# MCU.net
KiCad netlist of a schematic drawn in Altium Designer
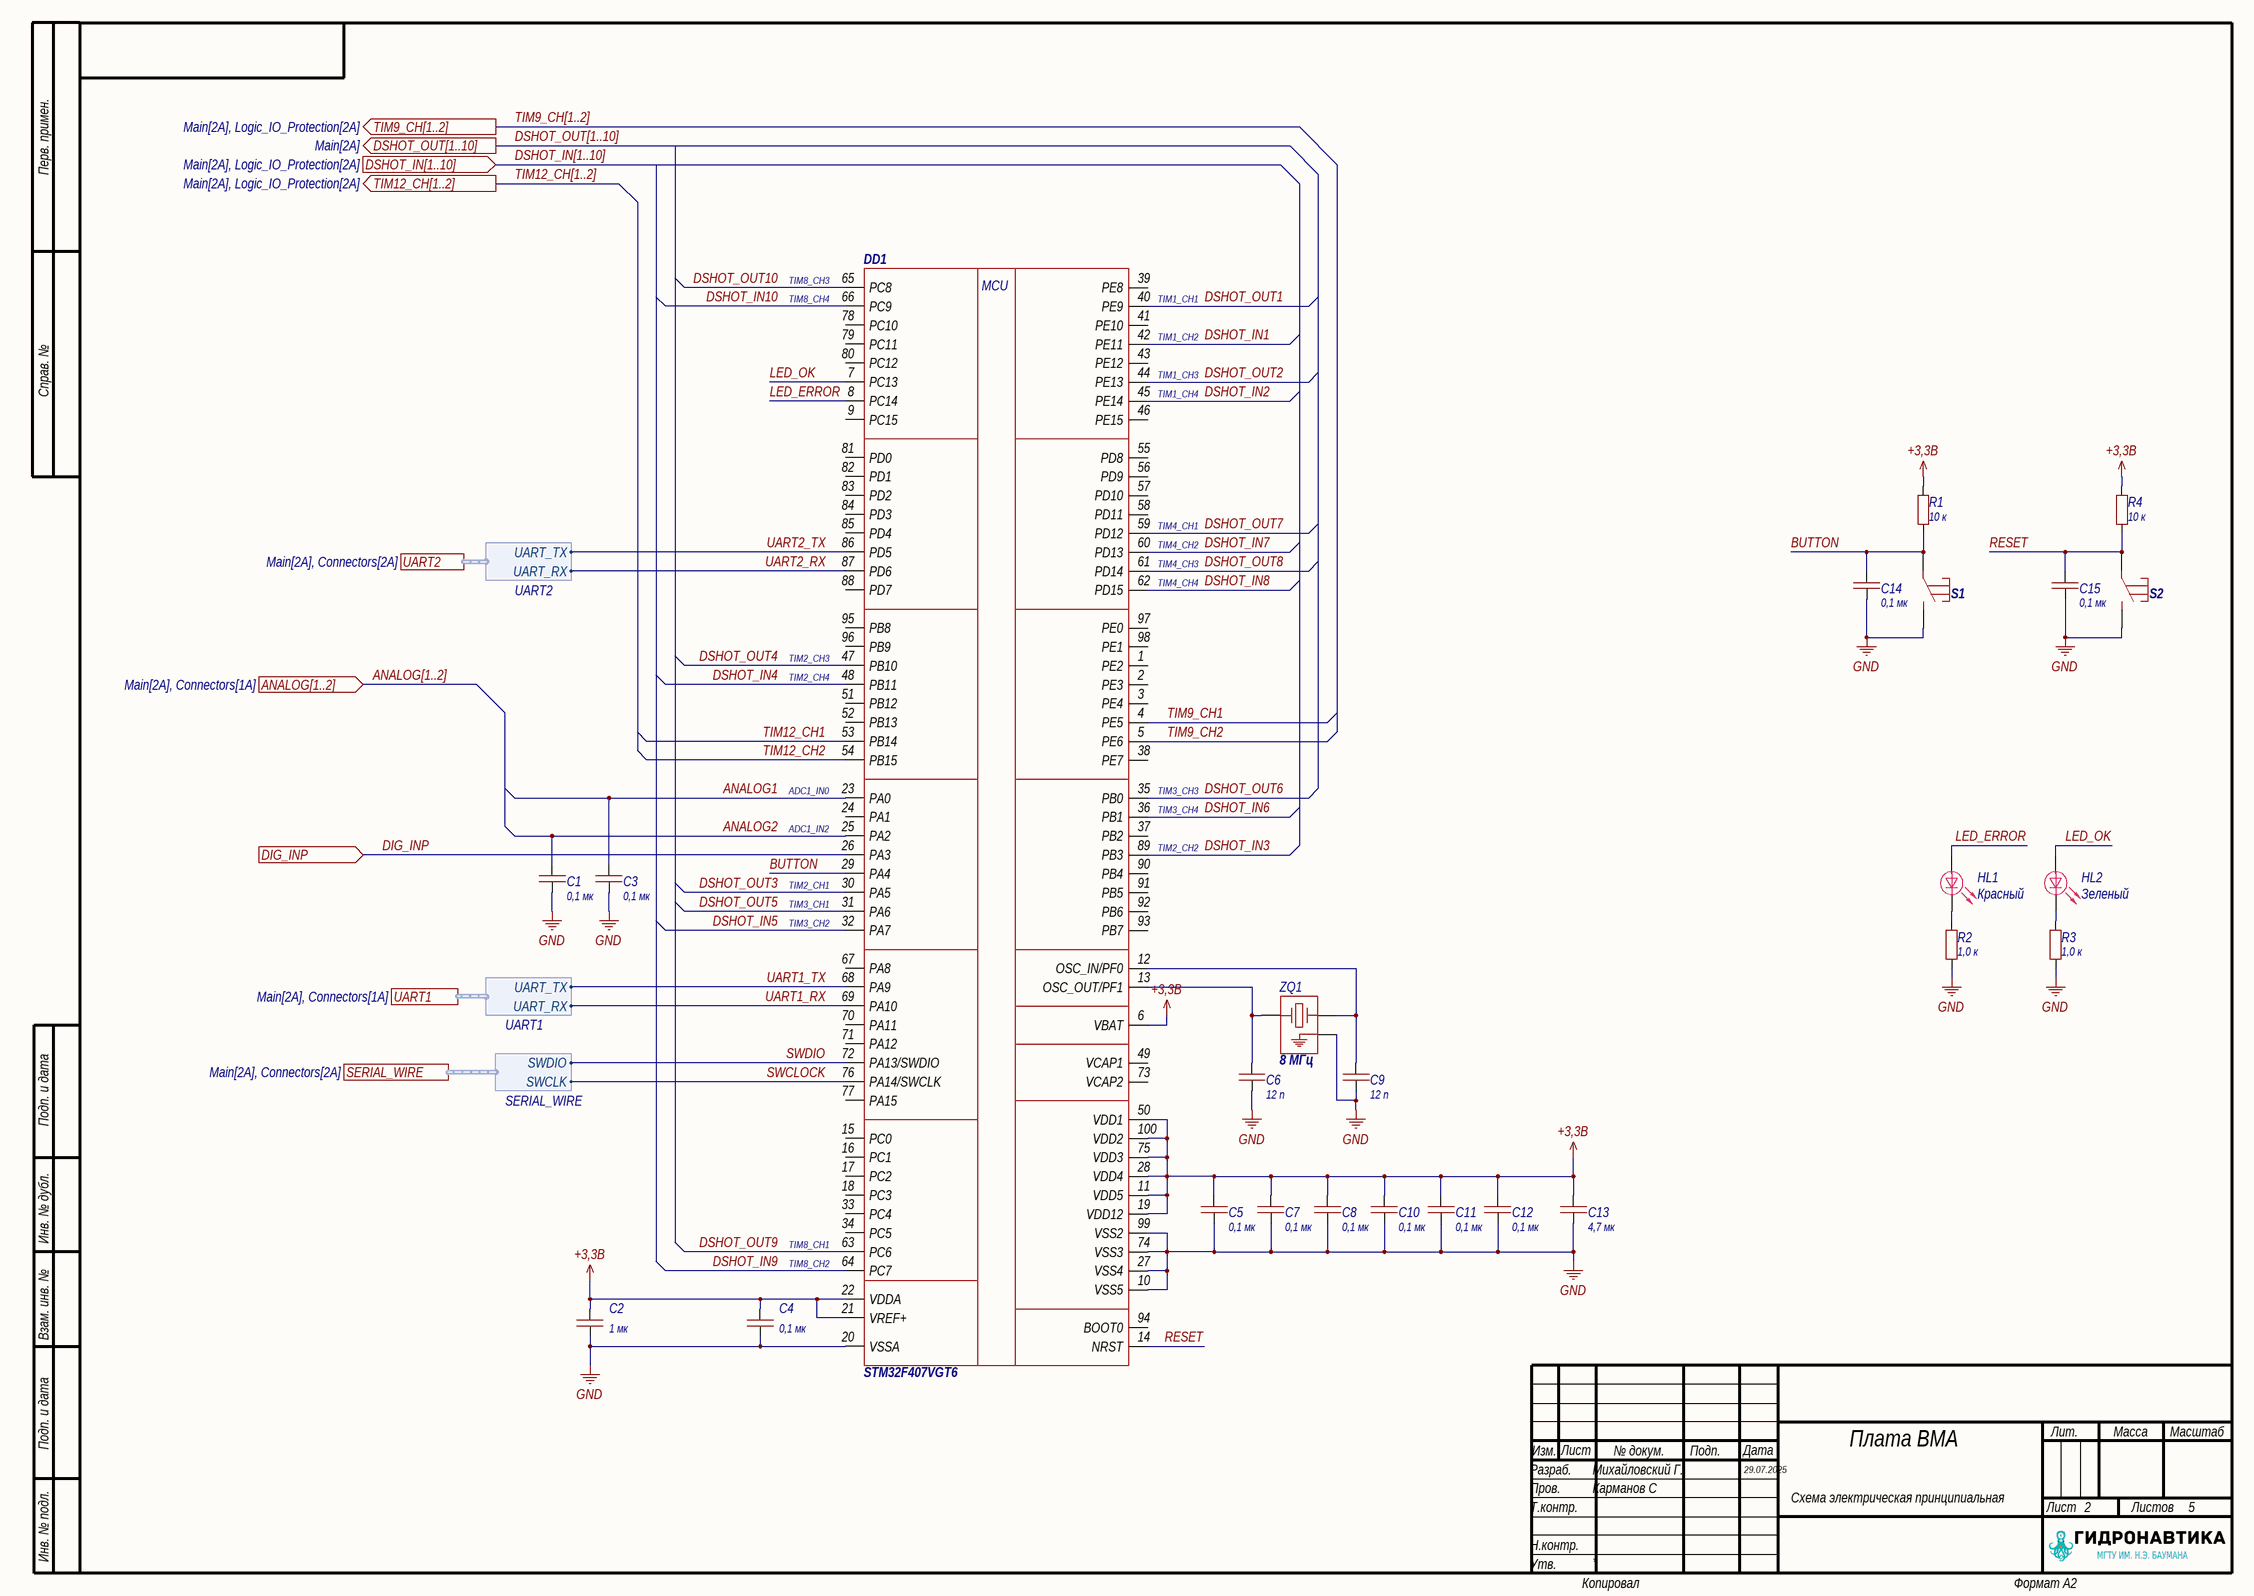
[diagram p0: MCU.SchDoc]

(export (version "E")
  (design (tool "Eeschema 10.0.6"))
  (components
    (comp (ref "C1")
      (value "0,1 мк")
      (footprint "0603C")
      (description "Конденсатор")
      (fields (field (name "PART NUMBER") "Capacitor_0,1u_10_50V_X7R_0603C") (field (name "TOLERANCE") "0,1"))
      (libsource (lib "Hydrolib") (part "Capacitor"))
    )
    (comp (ref "C2")
      (value "1 мк")
      (footprint "0603C")
      (description "Конденсатор")
      (fields (field (name "PART NUMBER") "Capacitor_1u_10_50V_X7R_0603C") (field (name "TOLERANCE") "0,1"))
      (libsource (lib "Hydrolib") (part "Capacitor"))
    )
    (comp (ref "C3")
      (value "0,1 мк")
      (footprint "0603C")
      (description "Конденсатор")
      (fields (field (name "PART NUMBER") "Capacitor_0,1u_10_50V_X7R_0603C") (field (name "TOLERANCE") "0,1"))
      (libsource (lib "Hydrolib") (part "Capacitor"))
    )
    (comp (ref "C4")
      (value "0,1 мк")
      (footprint "0603C")
      (description "Конденсатор")
      (fields (field (name "PART NUMBER") "Capacitor_0,1u_10_50V_X7R_0603C") (field (name "TOLERANCE") "0,1"))
      (libsource (lib "Hydrolib") (part "Capacitor"))
    )
    (comp (ref "C5")
      (value "0,1 мк")
      (footprint "0603C")
      (description "Конденсатор")
      (fields (field (name "PART NUMBER") "Capacitor_0,1u_10_50V_X7R_0603C") (field (name "TOLERANCE") "0,1"))
      (libsource (lib "Hydrolib") (part "Capacitor"))
    )
    (comp (ref "C6")
      (value "12 п")
      (footprint "0603C")
      (description "Конденсатор 12п")
      (fields (field (name "PART NUMBER") "Capacitor"))
      (libsource (lib "Hydrolib") (part "Capacitor"))
    )
    (comp (ref "C7")
      (value "0,1 мк")
      (footprint "0603C")
      (description "Конденсатор")
      (fields (field (name "PART NUMBER") "Capacitor_0,1u_10_50V_X7R_0603C") (field (name "TOLERANCE") "0,1"))
      (libsource (lib "Hydrolib") (part "Capacitor"))
    )
    (comp (ref "C8")
      (value "0,1 мк")
      (footprint "0603C")
      (description "Конденсатор")
      (fields (field (name "PART NUMBER") "Capacitor_0,1u_10_50V_X7R_0603C") (field (name "TOLERANCE") "0,1"))
      (libsource (lib "Hydrolib") (part "Capacitor"))
    )
    (comp (ref "C9")
      (value "12 п")
      (footprint "0603C")
      (description "Конденсатор 12п")
      (fields (field (name "PART NUMBER") "Capacitor"))
      (libsource (lib "Hydrolib") (part "Capacitor"))
    )
    (comp (ref "C10")
      (value "0,1 мк")
      (footprint "0603C")
      (description "Конденсатор")
      (fields (field (name "PART NUMBER") "Capacitor_0,1u_10_50V_X7R_0603C") (field (name "TOLERANCE") "0,1"))
      (libsource (lib "Hydrolib") (part "Capacitor"))
    )
    (comp (ref "C11")
      (value "0,1 мк")
      (footprint "0603C")
      (description "Конденсатор")
      (fields (field (name "PART NUMBER") "Capacitor_0,1u_10_50V_X7R_0603C") (field (name "TOLERANCE") "0,1"))
      (libsource (lib "Hydrolib") (part "Capacitor"))
    )
    (comp (ref "C12")
      (value "0,1 мк")
      (footprint "0603C")
      (description "Конденсатор")
      (fields (field (name "PART NUMBER") "Capacitor_0,1u_10_50V_X7R_0603C") (field (name "TOLERANCE") "0,1"))
      (libsource (lib "Hydrolib") (part "Capacitor"))
    )
    (comp (ref "C13")
      (value "4,7 мк")
      (footprint "1206C")
      (description "Конденсатор")
      (fields (field (name "PART NUMBER") "Capacitor_4,7u_10_50V_X7R_1206C") (field (name "TOLERANCE") "0,1"))
      (libsource (lib "Hydrolib") (part "Capacitor"))
    )
    (comp (ref "C14")
      (value "0,1 мк")
      (footprint "0603C")
      (description "Конденсатор")
      (fields (field (name "PART NUMBER") "Capacitor_0,1u_10_50V_X7R_0603C") (field (name "TOLERANCE") "0,1"))
      (libsource (lib "Hydrolib") (part "Capacitor"))
    )
    (comp (ref "C15")
      (value "0,1 мк")
      (footprint "0603C")
      (description "Конденсатор")
      (fields (field (name "PART NUMBER") "Capacitor_0,1u_10_50V_X7R_0603C") (field (name "TOLERANCE") "0,1"))
      (libsource (lib "Hydrolib") (part "Capacitor"))
    )
    (comp (ref "DD1")
      (value "STM32F407VGT6")
      (footprint "LQFP100")
      (description "Микроконтроллер")
      (libsource (lib "Hydrolib") (part "STM32F407VGT6"))
    )
    (comp (ref "HL1")
      (value "LED")
      (footprint "0805D")
      (description "Светодиод")
      (fields (field (name "COLOR") "Красный"))
      (libsource (lib "Hydrolib") (part "LED"))
    )
    (comp (ref "HL2")
      (value "LED")
      (footprint "0805D")
      (description "Светодиод")
      (fields (field (name "COLOR") "Зеленый"))
      (libsource (lib "Hydrolib") (part "LED"))
    )
    (comp (ref "R1")
      (value "10 к")
      (footprint "0603R")
      (description "Резистор номиналом 10 кОм и точностью 1%")
      (fields (field (name "PART NUMBER") "Resistor_10k_1_0603") (field (name "TOLERANCE") "1%"))
      (libsource (lib "Hydrolib") (part "Resistor"))
    )
    (comp (ref "R2")
      (value "1,0 к")
      (footprint "0603R")
      (description "Резистор номиналом 1,0 кОм и точностью 1%")
      (fields (field (name "PART NUMBER") "Resistor_1.0k_1_0603") (field (name "TOLERANCE") "1%"))
      (libsource (lib "Hydrolib") (part "Resistor"))
    )
    (comp (ref "R3")
      (value "1,0 к")
      (footprint "0603R")
      (description "Резистор номиналом 1,0 кОм и точностью 1%")
      (fields (field (name "PART NUMBER") "Resistor_1.0k_1_0603") (field (name "TOLERANCE") "1%"))
      (libsource (lib "Hydrolib") (part "Resistor"))
    )
    (comp (ref "R4")
      (value "10 к")
      (footprint "0603R")
      (description "Резистор номиналом 10 кОм и точностью 1%")
      (fields (field (name "PART NUMBER") "Resistor_10k_1_0603") (field (name "TOLERANCE") "1%"))
      (libsource (lib "Hydrolib") (part "Resistor"))
    )
    (comp (ref "S1")
      (value "TSS-TD-19XA-XTR")
      (footprint "TSS-TD-19XA-XTR")
      (description "Тактовая кнопка")
      (libsource (lib "Hydrolib") (part "Tact_button"))
    )
    (comp (ref "S2")
      (value "TSS-TD-19XA-XTR")
      (footprint "TSS-TD-19XA-XTR")
      (description "Тактовая кнопка")
      (libsource (lib "Hydrolib") (part "Tact_button"))
    )
    (comp (ref "ZQ1")
      (value "8 МГц")
      (footprint "QSMD3.2x2.5")
      (description "Кварцевый резонатор с входом земли")
      (fields (field (name "PART NUMBER") "XTAL_GND"))
      (libsource (lib "Hydrolib") (part "XTAL_GND"))
    )
  )
  (nets
    (net (code "4") (name "+3,3В") (class "Default")
      (node (ref "C10") (pin "2") (pinfunction "2_2") (pintype "passive"))
      (node (ref "C11") (pin "2") (pinfunction "2_2") (pintype "passive"))
      (node (ref "C12") (pin "2") (pinfunction "2_2") (pintype "passive"))
      (node (ref "C13") (pin "2") (pinfunction "2_2") (pintype "passive"))
      (node (ref "C2") (pin "2") (pinfunction "2_2") (pintype "passive"))
      (node (ref "C4") (pin "2") (pinfunction "2_2") (pintype "passive"))
      (node (ref "C5") (pin "2") (pinfunction "2_2") (pintype "passive"))
      (node (ref "C7") (pin "2") (pinfunction "2_2") (pintype "passive"))
      (node (ref "C8") (pin "2") (pinfunction "2_2") (pintype "passive"))
      (node (ref "DD1") (pin "100") (pinfunction "VDD2_100") (pintype "passive"))
      (node (ref "DD1") (pin "11") (pinfunction "VDD5_11") (pintype "passive"))
      (node (ref "DD1") (pin "19") (pinfunction "VDD12_19") (pintype "passive"))
      (node (ref "DD1") (pin "21") (pinfunction "VREF+_21") (pintype "passive"))
      (node (ref "DD1") (pin "22") (pinfunction "VDDA_22") (pintype "passive"))
      (node (ref "DD1") (pin "28") (pinfunction "VDD4_28") (pintype "passive"))
      (node (ref "DD1") (pin "50") (pinfunction "VDD1_50") (pintype "passive"))
      (node (ref "DD1") (pin "6") (pinfunction "VBAT_6") (pintype "passive"))
      (node (ref "DD1") (pin "75") (pinfunction "VDD3_75") (pintype "passive"))
      (node (ref "R1") (pin "2") (pinfunction "2_2") (pintype "passive"))
      (node (ref "R4") (pin "2") (pinfunction "2_2") (pintype "passive"))
    )
    (net (code "5") (name "/ANALOG1") (class "Default")
      (node (ref "C3") (pin "2") (pinfunction "2_2") (pintype "passive"))
      (node (ref "DD1") (pin "23") (pinfunction "PA0_23") (pintype "passive"))
    )
    (net (code "6") (name "/ANALOG2") (class "Default")
      (node (ref "C1") (pin "2") (pinfunction "2_2") (pintype "passive"))
      (node (ref "DD1") (pin "25") (pinfunction "PA2_25") (pintype "passive"))
    )
    (net (code "8") (name "/BUTTON") (class "Default")
      (node (ref "C14") (pin "2") (pinfunction "2_2") (pintype "passive"))
      (node (ref "DD1") (pin "29") (pinfunction "PA4_29") (pintype "passive"))
      (node (ref "R1") (pin "1") (pinfunction "1_1") (pintype "passive"))
      (node (ref "S1") (pin "1") (pinfunction "1_1") (pintype "passive"))
    )
    (net (code "9") (name "/DIG_INP") (class "Default")
      (node (ref "DD1") (pin "26") (pinfunction "PA3_26") (pintype "passive"))
    )
    (net (code "10") (name "/DSHOT_IN1") (class "Default")
      (node (ref "DD1") (pin "42") (pinfunction "PE11_42") (pintype "passive"))
    )
    (net (code "11") (name "/DSHOT_IN2") (class "Default")
      (node (ref "DD1") (pin "45") (pinfunction "PE14_45") (pintype "passive"))
    )
    (net (code "12") (name "/DSHOT_IN3") (class "Default")
      (node (ref "DD1") (pin "89") (pinfunction "PB3_89") (pintype "passive"))
    )
    (net (code "13") (name "/DSHOT_IN4") (class "Default")
      (node (ref "DD1") (pin "48") (pinfunction "PB11_48") (pintype "passive"))
    )
    (net (code "14") (name "/DSHOT_IN5") (class "Default")
      (node (ref "DD1") (pin "32") (pinfunction "PA7_32") (pintype "passive"))
    )
    (net (code "15") (name "/DSHOT_IN6") (class "Default")
      (node (ref "DD1") (pin "36") (pinfunction "PB1_36") (pintype "passive"))
    )
    (net (code "16") (name "/DSHOT_IN7") (class "Default")
      (node (ref "DD1") (pin "60") (pinfunction "PD13_60") (pintype "passive"))
    )
    (net (code "17") (name "/DSHOT_IN8") (class "Default")
      (node (ref "DD1") (pin "62") (pinfunction "PD15_62") (pintype "passive"))
    )
    (net (code "18") (name "/DSHOT_IN9") (class "Default")
      (node (ref "DD1") (pin "64") (pinfunction "PC7_64") (pintype "passive"))
    )
    (net (code "19") (name "/DSHOT_IN10") (class "Default")
      (node (ref "DD1") (pin "66") (pinfunction "PC9_66") (pintype "passive"))
    )
    (net (code "21") (name "/DSHOT_OUT1") (class "Default")
      (node (ref "DD1") (pin "40") (pinfunction "PE9_40") (pintype "passive"))
    )
    (net (code "22") (name "/DSHOT_OUT2") (class "Default")
      (node (ref "DD1") (pin "44") (pinfunction "PE13_44") (pintype "passive"))
    )
    (net (code "23") (name "/DSHOT_OUT3") (class "Default")
      (node (ref "DD1") (pin "30") (pinfunction "PA5_30") (pintype "passive"))
    )
    (net (code "24") (name "/DSHOT_OUT4") (class "Default")
      (node (ref "DD1") (pin "47") (pinfunction "PB10_47") (pintype "passive"))
    )
    (net (code "25") (name "/DSHOT_OUT5") (class "Default")
      (node (ref "DD1") (pin "31") (pinfunction "PA6_31") (pintype "passive"))
    )
    (net (code "26") (name "/DSHOT_OUT6") (class "Default")
      (node (ref "DD1") (pin "35") (pinfunction "PB0_35") (pintype "passive"))
    )
    (net (code "27") (name "/DSHOT_OUT7") (class "Default")
      (node (ref "DD1") (pin "59") (pinfunction "PD12_59") (pintype "passive"))
    )
    (net (code "28") (name "/DSHOT_OUT8") (class "Default")
      (node (ref "DD1") (pin "61") (pinfunction "PD14_61") (pintype "passive"))
    )
    (net (code "29") (name "/DSHOT_OUT9") (class "Default")
      (node (ref "DD1") (pin "63") (pinfunction "PC6_63") (pintype "passive"))
    )
    (net (code "30") (name "/DSHOT_OUT10") (class "Default")
      (node (ref "DD1") (pin "65") (pinfunction "PC8_65") (pintype "passive"))
    )
    (net (code "32") (name "/LED_ERROR") (class "Default")
      (node (ref "DD1") (pin "8") (pinfunction "PC14_8") (pintype "passive"))
      (node (ref "HL1") (pin "1") (pinfunction "1_1") (pintype "passive"))
    )
    (net (code "33") (name "/LED_OK") (class "Default")
      (node (ref "DD1") (pin "7") (pinfunction "PC13_7") (pintype "passive"))
      (node (ref "HL2") (pin "1") (pinfunction "1_1") (pintype "passive"))
    )
    (net (code "34") (name "/RESET") (class "Default")
      (node (ref "C15") (pin "2") (pinfunction "2_2") (pintype "passive"))
      (node (ref "DD1") (pin "14") (pinfunction "NRST_14") (pintype "passive"))
      (node (ref "R4") (pin "1") (pinfunction "1_1") (pintype "passive"))
      (node (ref "S2") (pin "1") (pinfunction "1_1") (pintype "passive"))
    )
    (net (code "35") (name "/SWCLOCK") (class "Default")
      (node (ref "DD1") (pin "76") (pinfunction "PA14/SWCLK_76") (pintype "passive"))
    )
    (net (code "36") (name "/SWDIO") (class "Default")
      (node (ref "DD1") (pin "72") (pinfunction "PA13/SWDIO_72") (pintype "passive"))
    )
    (net (code "37") (name "/TIM9_CH1") (class "Default")
      (node (ref "DD1") (pin "4") (pinfunction "PE5_4") (pintype "passive"))
    )
    (net (code "38") (name "/TIM9_CH2") (class "Default")
      (node (ref "DD1") (pin "5") (pinfunction "PE6_5") (pintype "passive"))
    )
    (net (code "40") (name "/TIM12_CH1") (class "Default")
      (node (ref "DD1") (pin "53") (pinfunction "PB14_53") (pintype "passive"))
    )
    (net (code "41") (name "/TIM12_CH2") (class "Default")
      (node (ref "DD1") (pin "54") (pinfunction "PB15_54") (pintype "passive"))
    )
    (net (code "43") (name "/UART1_RX") (class "Default")
      (node (ref "DD1") (pin "69") (pinfunction "PA10_69") (pintype "passive"))
    )
    (net (code "44") (name "/UART1_TX") (class "Default")
      (node (ref "DD1") (pin "68") (pinfunction "PA9_68") (pintype "passive"))
    )
    (net (code "45") (name "/UART2_RX") (class "Default")
      (node (ref "DD1") (pin "87") (pinfunction "PD6_87") (pintype "passive"))
    )
    (net (code "46") (name "/UART2_TX") (class "Default")
      (node (ref "DD1") (pin "86") (pinfunction "PD5_86") (pintype "passive"))
    )
    (net (code "50") (name "GND") (class "Default")
      (node (ref "C1") (pin "1") (pinfunction "1_1") (pintype "passive"))
      (node (ref "C10") (pin "1") (pinfunction "1_1") (pintype "passive"))
      (node (ref "C11") (pin "1") (pinfunction "1_1") (pintype "passive"))
      (node (ref "C12") (pin "1") (pinfunction "1_1") (pintype "passive"))
      (node (ref "C13") (pin "1") (pinfunction "1_1") (pintype "passive"))
      (node (ref "C14") (pin "1") (pinfunction "1_1") (pintype "passive"))
      (node (ref "C15") (pin "1") (pinfunction "1_1") (pintype "passive"))
      (node (ref "C2") (pin "1") (pinfunction "1_1") (pintype "passive"))
      (node (ref "C3") (pin "1") (pinfunction "1_1") (pintype "passive"))
      (node (ref "C4") (pin "1") (pinfunction "1_1") (pintype "passive"))
      (node (ref "C5") (pin "1") (pinfunction "1_1") (pintype "passive"))
      (node (ref "C6") (pin "1") (pinfunction "1_1") (pintype "passive"))
      (node (ref "C7") (pin "1") (pinfunction "1_1") (pintype "passive"))
      (node (ref "C8") (pin "1") (pinfunction "1_1") (pintype "passive"))
      (node (ref "C9") (pin "1") (pinfunction "1_1") (pintype "passive"))
      (node (ref "DD1") (pin "10") (pinfunction "VSS5_10") (pintype "passive"))
      (node (ref "DD1") (pin "20") (pinfunction "VSSA_20") (pintype "passive"))
      (node (ref "DD1") (pin "27") (pinfunction "VSS4_27") (pintype "passive"))
      (node (ref "DD1") (pin "74") (pinfunction "VSS3_74") (pintype "passive"))
      (node (ref "DD1") (pin "99") (pinfunction "VSS2_99") (pintype "passive"))
      (node (ref "R2") (pin "1") (pinfunction "1_1") (pintype "passive"))
      (node (ref "R3") (pin "1") (pinfunction "1_1") (pintype "passive"))
      (node (ref "S1") (pin "2") (pinfunction "2_2") (pintype "passive"))
      (node (ref "S2") (pin "2") (pinfunction "2_2") (pintype "passive"))
      (node (ref "ZQ1") (pin "3") (pinfunction "3_3") (pintype "passive"))
    )
    (net (code "51") (name "Net-(DD1-OSC_IN{slash}PF0)") (class "Default")
      (node (ref "C9") (pin "2") (pinfunction "2_2") (pintype "passive"))
      (node (ref "DD1") (pin "12") (pinfunction "OSC_IN/PF0_12") (pintype "passive"))
      (node (ref "ZQ1") (pin "2") (pinfunction "2_2") (pintype "passive"))
    )
    (net (code "52") (name "Net-(DD1-OSC_OUT{slash}PF1)") (class "Default")
      (node (ref "C6") (pin "2") (pinfunction "2_2") (pintype "passive"))
      (node (ref "DD1") (pin "13") (pinfunction "OSC_OUT/PF1_13") (pintype "passive"))
      (node (ref "ZQ1") (pin "1") (pinfunction "1_1") (pintype "passive"))
    )
    (net (code "53") (name "Net-(HL1-Pad2)") (class "Default")
      (node (ref "HL1") (pin "2") (pinfunction "2_2") (pintype "passive"))
      (node (ref "R2") (pin "2") (pinfunction "2_2") (pintype "passive"))
    )
    (net (code "54") (name "Net-(HL2-Pad2)") (class "Default")
      (node (ref "HL2") (pin "2") (pinfunction "2_2") (pintype "passive"))
      (node (ref "R3") (pin "2") (pinfunction "2_2") (pintype "passive"))
    )
    (net (code "55") (name "unconnected-(DD1-BOOT0-Pad94)") (class "Default")
      (node (ref "DD1") (pin "94") (pinfunction "BOOT0_94") (pintype "passive"))
    )
    (net (code "56") (name "unconnected-(DD1-PA1-Pad24)") (class "Default")
      (node (ref "DD1") (pin "24") (pinfunction "PA1_24") (pintype "passive"))
    )
    (net (code "57") (name "unconnected-(DD1-PA8-Pad67)") (class "Default")
      (node (ref "DD1") (pin "67") (pinfunction "PA8_67") (pintype "passive"))
    )
    (net (code "58") (name "unconnected-(DD1-PA11-Pad70)") (class "Default")
      (node (ref "DD1") (pin "70") (pinfunction "PA11_70") (pintype "passive"))
    )
    (net (code "59") (name "unconnected-(DD1-PA12-Pad71)") (class "Default")
      (node (ref "DD1") (pin "71") (pinfunction "PA12_71") (pintype "passive"))
    )
    (net (code "60") (name "unconnected-(DD1-PA15-Pad77)") (class "Default")
      (node (ref "DD1") (pin "77") (pinfunction "PA15_77") (pintype "passive"))
    )
    (net (code "61") (name "unconnected-(DD1-PB2-Pad37)") (class "Default")
      (node (ref "DD1") (pin "37") (pinfunction "PB2_37") (pintype "passive"))
    )
    (net (code "62") (name "unconnected-(DD1-PB4-Pad90)") (class "Default")
      (node (ref "DD1") (pin "90") (pinfunction "PB4_90") (pintype "passive"))
    )
    (net (code "63") (name "unconnected-(DD1-PB5-Pad91)") (class "Default")
      (node (ref "DD1") (pin "91") (pinfunction "PB5_91") (pintype "passive"))
    )
    (net (code "64") (name "unconnected-(DD1-PB6-Pad92)") (class "Default")
      (node (ref "DD1") (pin "92") (pinfunction "PB6_92") (pintype "passive"))
    )
    (net (code "65") (name "unconnected-(DD1-PB7-Pad93)") (class "Default")
      (node (ref "DD1") (pin "93") (pinfunction "PB7_93") (pintype "passive"))
    )
    (net (code "66") (name "unconnected-(DD1-PB8-Pad95)") (class "Default")
      (node (ref "DD1") (pin "95") (pinfunction "PB8_95") (pintype "passive"))
    )
    (net (code "67") (name "unconnected-(DD1-PB9-Pad96)") (class "Default")
      (node (ref "DD1") (pin "96") (pinfunction "PB9_96") (pintype "passive"))
    )
    (net (code "68") (name "unconnected-(DD1-PB12-Pad51)") (class "Default")
      (node (ref "DD1") (pin "51") (pinfunction "PB12_51") (pintype "passive"))
    )
    (net (code "69") (name "unconnected-(DD1-PB13-Pad52)") (class "Default")
      (node (ref "DD1") (pin "52") (pinfunction "PB13_52") (pintype "passive"))
    )
    (net (code "70") (name "unconnected-(DD1-PC0-Pad15)") (class "Default")
      (node (ref "DD1") (pin "15") (pinfunction "PC0_15") (pintype "passive"))
    )
    (net (code "71") (name "unconnected-(DD1-PC1-Pad16)") (class "Default")
      (node (ref "DD1") (pin "16") (pinfunction "PC1_16") (pintype "passive"))
    )
    (net (code "72") (name "unconnected-(DD1-PC2-Pad17)") (class "Default")
      (node (ref "DD1") (pin "17") (pinfunction "PC2_17") (pintype "passive"))
    )
    (net (code "73") (name "unconnected-(DD1-PC3-Pad18)") (class "Default")
      (node (ref "DD1") (pin "18") (pinfunction "PC3_18") (pintype "passive"))
    )
    (net (code "74") (name "unconnected-(DD1-PC4-Pad33)") (class "Default")
      (node (ref "DD1") (pin "33") (pinfunction "PC4_33") (pintype "passive"))
    )
    (net (code "75") (name "unconnected-(DD1-PC5-Pad34)") (class "Default")
      (node (ref "DD1") (pin "34") (pinfunction "PC5_34") (pintype "passive"))
    )
    (net (code "76") (name "unconnected-(DD1-PC10-Pad78)") (class "Default")
      (node (ref "DD1") (pin "78") (pinfunction "PC10_78") (pintype "passive"))
    )
    (net (code "77") (name "unconnected-(DD1-PC11-Pad79)") (class "Default")
      (node (ref "DD1") (pin "79") (pinfunction "PC11_79") (pintype "passive"))
    )
    (net (code "78") (name "unconnected-(DD1-PC12-Pad80)") (class "Default")
      (node (ref "DD1") (pin "80") (pinfunction "PC12_80") (pintype "passive"))
    )
    (net (code "79") (name "unconnected-(DD1-PC15-Pad9)") (class "Default")
      (node (ref "DD1") (pin "9") (pinfunction "PC15_9") (pintype "passive"))
    )
    (net (code "80") (name "unconnected-(DD1-PD0-Pad81)") (class "Default")
      (node (ref "DD1") (pin "81") (pinfunction "PD0_81") (pintype "passive"))
    )
    (net (code "81") (name "unconnected-(DD1-PD1-Pad82)") (class "Default")
      (node (ref "DD1") (pin "82") (pinfunction "PD1_82") (pintype "passive"))
    )
    (net (code "82") (name "unconnected-(DD1-PD2-Pad83)") (class "Default")
      (node (ref "DD1") (pin "83") (pinfunction "PD2_83") (pintype "passive"))
    )
    (net (code "83") (name "unconnected-(DD1-PD3-Pad84)") (class "Default")
      (node (ref "DD1") (pin "84") (pinfunction "PD3_84") (pintype "passive"))
    )
    (net (code "84") (name "unconnected-(DD1-PD4-Pad85)") (class "Default")
      (node (ref "DD1") (pin "85") (pinfunction "PD4_85") (pintype "passive"))
    )
    (net (code "85") (name "unconnected-(DD1-PD7-Pad88)") (class "Default")
      (node (ref "DD1") (pin "88") (pinfunction "PD7_88") (pintype "passive"))
    )
    (net (code "86") (name "unconnected-(DD1-PD8-Pad55)") (class "Default")
      (node (ref "DD1") (pin "55") (pinfunction "PD8_55") (pintype "passive"))
    )
    (net (code "87") (name "unconnected-(DD1-PD9-Pad56)") (class "Default")
      (node (ref "DD1") (pin "56") (pinfunction "PD9_56") (pintype "passive"))
    )
    (net (code "88") (name "unconnected-(DD1-PD10-Pad57)") (class "Default")
      (node (ref "DD1") (pin "57") (pinfunction "PD10_57") (pintype "passive"))
    )
    (net (code "89") (name "unconnected-(DD1-PD11-Pad58)") (class "Default")
      (node (ref "DD1") (pin "58") (pinfunction "PD11_58") (pintype "passive"))
    )
    (net (code "90") (name "unconnected-(DD1-PE0-Pad97)") (class "Default")
      (node (ref "DD1") (pin "97") (pinfunction "PE0_97") (pintype "passive"))
    )
    (net (code "91") (name "unconnected-(DD1-PE1-Pad98)") (class "Default")
      (node (ref "DD1") (pin "98") (pinfunction "PE1_98") (pintype "passive"))
    )
    (net (code "92") (name "unconnected-(DD1-PE2-Pad1)") (class "Default")
      (node (ref "DD1") (pin "1") (pinfunction "PE2_1") (pintype "passive"))
    )
    (net (code "93") (name "unconnected-(DD1-PE3-Pad2)") (class "Default")
      (node (ref "DD1") (pin "2") (pinfunction "PE3_2") (pintype "passive"))
    )
    (net (code "94") (name "unconnected-(DD1-PE4-Pad3)") (class "Default")
      (node (ref "DD1") (pin "3") (pinfunction "PE4_3") (pintype "passive"))
    )
    (net (code "95") (name "unconnected-(DD1-PE7-Pad38)") (class "Default")
      (node (ref "DD1") (pin "38") (pinfunction "PE7_38") (pintype "passive"))
    )
    (net (code "96") (name "unconnected-(DD1-PE8-Pad39)") (class "Default")
      (node (ref "DD1") (pin "39") (pinfunction "PE8_39") (pintype "passive"))
    )
    (net (code "97") (name "unconnected-(DD1-PE10-Pad41)") (class "Default")
      (node (ref "DD1") (pin "41") (pinfunction "PE10_41") (pintype "passive"))
    )
    (net (code "98") (name "unconnected-(DD1-PE12-Pad43)") (class "Default")
      (node (ref "DD1") (pin "43") (pinfunction "PE12_43") (pintype "passive"))
    )
    (net (code "99") (name "unconnected-(DD1-PE15-Pad46)") (class "Default")
      (node (ref "DD1") (pin "46") (pinfunction "PE15_46") (pintype "passive"))
    )
    (net (code "100") (name "unconnected-(DD1-VCAP1-Pad49)") (class "Default")
      (node (ref "DD1") (pin "49") (pinfunction "VCAP1_49") (pintype "passive"))
    )
    (net (code "101") (name "unconnected-(DD1-VCAP2-Pad73)") (class "Default")
      (node (ref "DD1") (pin "73") (pinfunction "VCAP2_73") (pintype "passive"))
    )
  )
)
